# Blinky.net
KiCad netlist of a schematic drawn in EAGLE
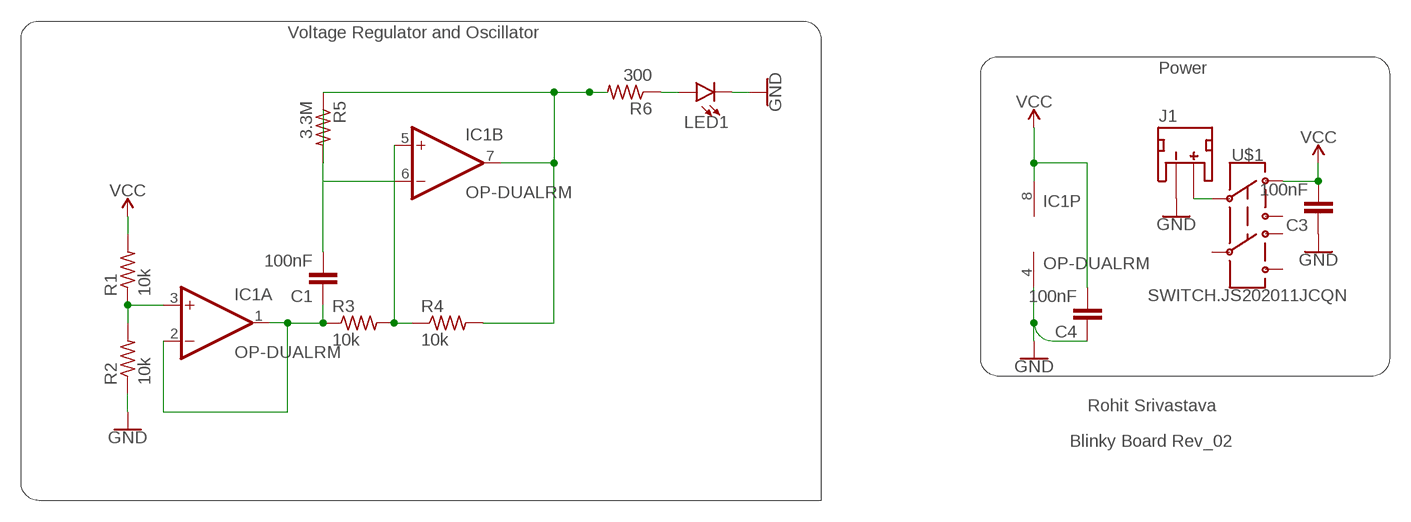
[diagram p0: schematic, sheet 1]

(export (version "E")
  (design (tool "Eeschema 10.0.6"))
  (components
    (comp (ref "C1")
      (value "100nF")
      (footprint "eagle-import:C0402")
      (libsource (lib "eagle-import") (part "CAPACITOR0402"))
    )
    (comp (ref "C3")
      (value "100nF")
      (footprint "eagle-import:C0402")
      (libsource (lib "eagle-import") (part "CAPACITOR0402"))
    )
    (comp (ref "C4")
      (value "100nF")
      (footprint "eagle-import:C0402")
      (libsource (lib "eagle-import") (part "CAPACITOR0402"))
    )
    (comp (ref "IC1")
      (value "OP-DUALRM")
      (footprint "eagle-import:MSOP08")
      (fields (field (name "MF") "ALTERA CORPORATION") (field (name "MPN") "AD8607ARMZ-REEL"))
      (libsource (lib "eagle-import") (part "OP-DUALRM"))
    )
    (comp (ref "J1")
      (value "JST_2MM_MALE")
      (footprint "eagle-import:JST-2-SMD")
      (libsource (lib "eagle-import") (part "JST_2MM_MALE"))
    )
    (comp (ref "LED1")
      (value "LED0603")
      (footprint "eagle-import:LED-0603")
      (libsource (lib "eagle-import") (part "LED0603"))
    )
    (comp (ref "R1")
      (value "10k")
      (footprint "eagle-import:R0402")
      (libsource (lib "eagle-import") (part "RESISTOR0402"))
    )
    (comp (ref "R2")
      (value "10k")
      (footprint "eagle-import:R0402")
      (libsource (lib "eagle-import") (part "RESISTOR0402"))
    )
    (comp (ref "R3")
      (value "10k")
      (footprint "eagle-import:R0402")
      (libsource (lib "eagle-import") (part "RESISTOR0402"))
    )
    (comp (ref "R4")
      (value "10k")
      (footprint "eagle-import:R0402")
      (libsource (lib "eagle-import") (part "RESISTOR0402"))
    )
    (comp (ref "R5")
      (value "3.3M")
      (footprint "eagle-import:R0402")
      (libsource (lib "eagle-import") (part "RESISTOR0402"))
    )
    (comp (ref "R6")
      (value "300")
      (footprint "eagle-import:R0402")
      (libsource (lib "eagle-import") (part "RESISTOR0402"))
    )
    (comp (ref "U$1")
      (value "SWITCH.JS202011JCQN")
      (footprint "eagle-import:SWITCH.00")
      (libsource (lib "eagle-import") (part "SWITCH.JS202011JCQN"))
    )
  )
  (nets
    (net (code "1") (name "GND") (class "Default")
      (node (ref "C3") (pin "1") (pinfunction "1_1") (pintype "passive"))
      (node (ref "C4") (pin "1") (pinfunction "1_1") (pintype "passive"))
      (node (ref "IC1") (pin "4") (pinfunction "V-_4") (pintype "power_in"))
      (node (ref "J1") (pin "1") (pinfunction "-_1") (pintype "bidirectional"))
      (node (ref "LED1") (pin "C") (pinfunction "C_C") (pintype "passive"))
      (node (ref "R2") (pin "1") (pinfunction "1_1") (pintype "passive"))
    )
    (net (code "2") (name "Net-(IC1A-+IN)") (class "Default")
      (node (ref "IC1") (pin "3") (pinfunction "+IN_3") (pintype "input"))
      (node (ref "R1") (pin "1") (pinfunction "1_1") (pintype "passive"))
      (node (ref "R2") (pin "2") (pinfunction "2_2") (pintype "passive"))
    )
    (net (code "3") (name "Net-(IC1A--IN)") (class "Default")
      (node (ref "C1") (pin "1") (pinfunction "1_1") (pintype "passive"))
      (node (ref "IC1") (pin "1") (pinfunction "OUT_1") (pintype "output"))
      (node (ref "IC1") (pin "2") (pinfunction "-IN_2") (pintype "input"))
      (node (ref "R3") (pin "1") (pinfunction "1_1") (pintype "passive"))
    )
    (net (code "4") (name "Net-(IC1B-+IN)") (class "Default")
      (node (ref "IC1") (pin "5") (pinfunction "+IN_5") (pintype "input"))
      (node (ref "R3") (pin "2") (pinfunction "2_2") (pintype "passive"))
      (node (ref "R4") (pin "1") (pinfunction "1_1") (pintype "passive"))
    )
    (net (code "5") (name "Net-(IC1B--IN)") (class "Default")
      (node (ref "C1") (pin "2") (pinfunction "2_2") (pintype "passive"))
      (node (ref "IC1") (pin "6") (pinfunction "-IN_6") (pintype "input"))
      (node (ref "R5") (pin "2") (pinfunction "2_2") (pintype "passive"))
    )
    (net (code "6") (name "Net-(IC1B-OUT)") (class "Default")
      (node (ref "IC1") (pin "7") (pinfunction "OUT_7") (pintype "output"))
      (node (ref "R4") (pin "2") (pinfunction "2_2") (pintype "passive"))
      (node (ref "R5") (pin "1") (pinfunction "1_1") (pintype "passive"))
      (node (ref "R6") (pin "2") (pinfunction "2_2") (pintype "passive"))
    )
    (net (code "7") (name "Net-(J1-+)") (class "Default")
      (node (ref "J1") (pin "2") (pinfunction "+_2") (pintype "bidirectional"))
      (node (ref "U$1") (pin "2") (pinfunction "2_2") (pintype "bidirectional"))
    )
    (net (code "8") (name "Net-(LED1-PadA)") (class "Default")
      (node (ref "LED1") (pin "A") (pinfunction "A_A") (pintype "passive"))
      (node (ref "R6") (pin "1") (pinfunction "1_1") (pintype "passive"))
    )
    (net (code "9") (name "VCC") (class "Default")
      (node (ref "C3") (pin "2") (pinfunction "2_2") (pintype "passive"))
      (node (ref "C4") (pin "2") (pinfunction "2_2") (pintype "passive"))
      (node (ref "IC1") (pin "8") (pinfunction "V+_8") (pintype "power_in"))
      (node (ref "R1") (pin "2") (pinfunction "2_2") (pintype "passive"))
      (node (ref "U$1") (pin "1") (pinfunction "1_1") (pintype "bidirectional"))
    )
    (net (code "10") (name "unconnected-(J1-PAD1-PadNC1)") (class "Default")
      (node (ref "J1") (pin "NC1") (pinfunction "PAD1_NC1") (pintype "bidirectional"))
    )
    (net (code "11") (name "unconnected-(J1-PAD2-PadNC2)") (class "Default")
      (node (ref "J1") (pin "NC2") (pinfunction "PAD2_NC2") (pintype "bidirectional"))
    )
    (net (code "12") (name "unconnected-(U$1-Pad3)") (class "Default")
      (node (ref "U$1") (pin "3") (pinfunction "3_3") (pintype "bidirectional"))
    )
    (net (code "13") (name "unconnected-(U$1-Pad5)") (class "Default")
      (node (ref "U$1") (pin "5") (pinfunction "5_5") (pintype "bidirectional"))
    )
    (net (code "14") (name "unconnected-(U$1-Pad6)") (class "Default")
      (node (ref "U$1") (pin "6") (pinfunction "6_6") (pintype "bidirectional"))
    )
    (net (code "15") (name "unconnected-(U$1-Pad7)") (class "Default")
      (node (ref "U$1") (pin "7") (pinfunction "7_7") (pintype "bidirectional"))
    )
  )
)
